# Power.net
KiCad netlist of a schematic drawn in Altium Designer
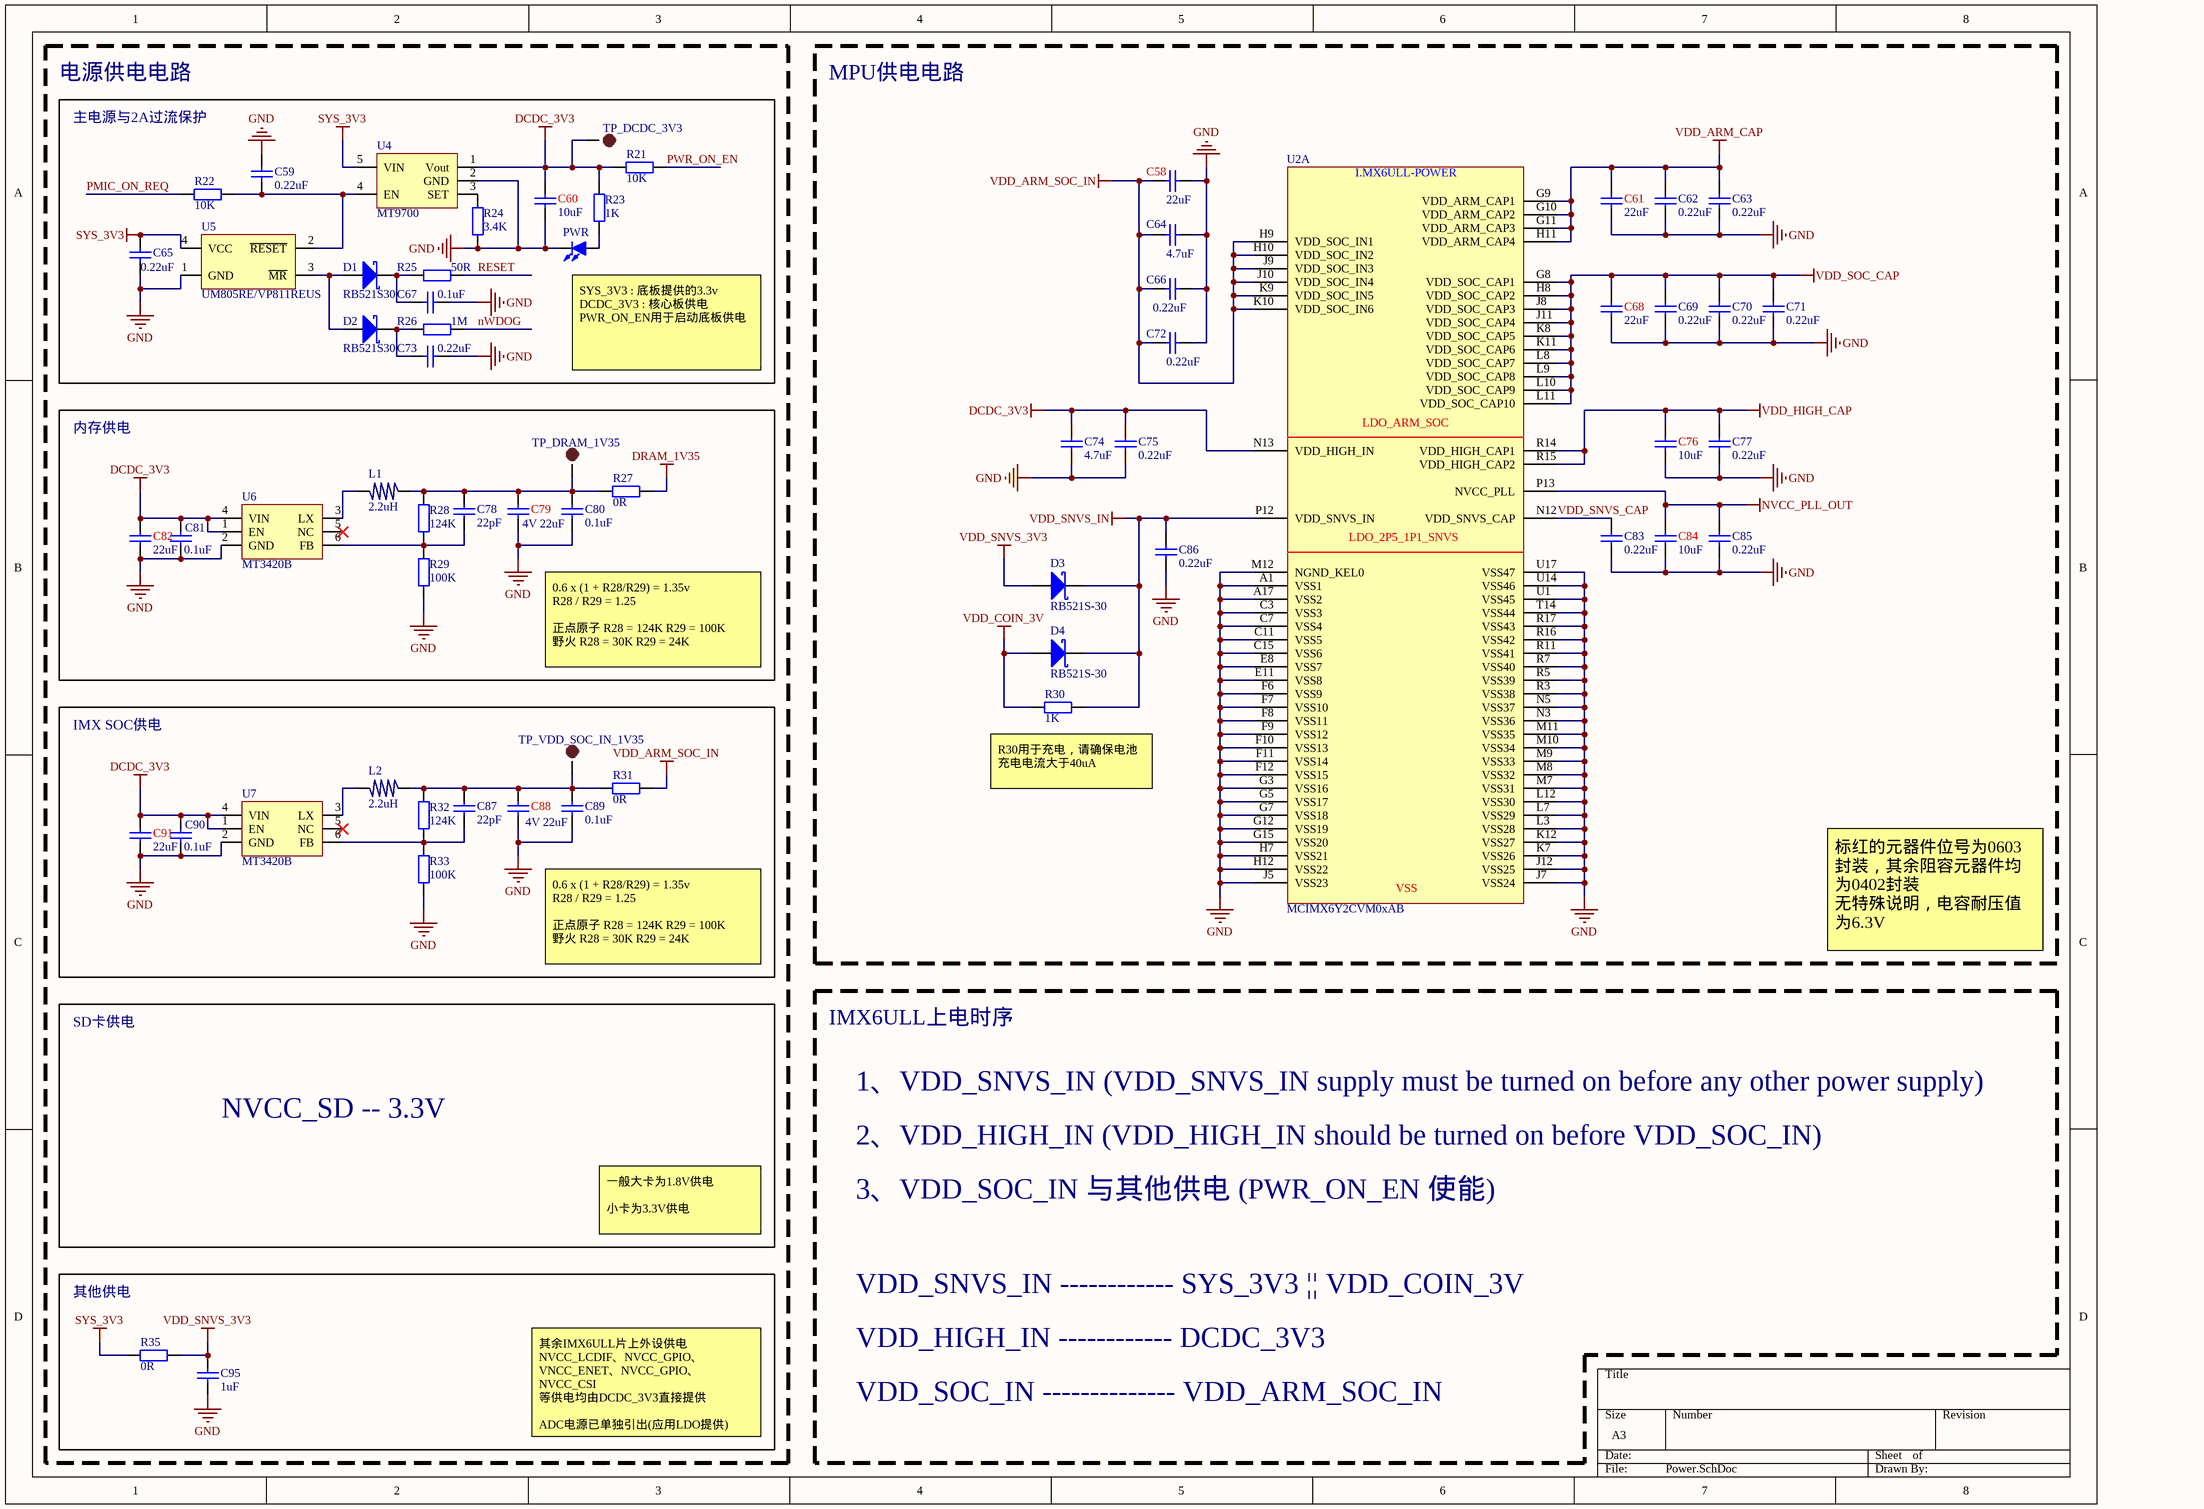
[diagram p0: Power.SchDoc]

(export (version "E")
  (design (tool "Eeschema 10.0.6"))
  (components
    (comp (ref "C58")
      (value "22uF")
      (footprint "0603_C _MINI")
      (description "贴片电容")
      (libsource (lib "My_Devices") (part "0603_C_MINI"))
    )
    (comp (ref "C59")
      (value "0.22uF")
      (footprint "0402_C")
      (description "贴片电容")
      (libsource (lib "My_Devices") (part "0402_C"))
    )
    (comp (ref "C60")
      (value "10uF")
      (footprint "0603_C _MINI")
      (description "贴片电容")
      (libsource (lib "My_Devices") (part "0603_C_MINI"))
    )
    (comp (ref "C61")
      (value "22uF")
      (footprint "0603_C _MINI")
      (description "贴片电容")
      (libsource (lib "My_Devices") (part "0603_C_MINI"))
    )
    (comp (ref "C62")
      (value "0.22uF")
      (footprint "0402_C")
      (description "贴片电容")
      (libsource (lib "My_Devices") (part "0402_C"))
    )
    (comp (ref "C63")
      (value "0.22uF")
      (footprint "0402_C")
      (description "贴片电容")
      (libsource (lib "My_Devices") (part "0402_C"))
    )
    (comp (ref "C64")
      (value "4.7uF")
      (footprint "0402_C")
      (description "贴片电容")
      (libsource (lib "My_Devices") (part "0402_C"))
    )
    (comp (ref "C65")
      (value "0.22uF")
      (footprint "0402_C")
      (description "贴片电容")
      (libsource (lib "My_Devices") (part "0402_C"))
    )
    (comp (ref "C66")
      (value "0.22uF")
      (footprint "0402_C")
      (description "贴片电容")
      (libsource (lib "My_Devices") (part "0402_C"))
    )
    (comp (ref "C67")
      (value "0.1uF")
      (footprint "0402_C")
      (description "贴片电容")
      (libsource (lib "My_Devices") (part "0402_C"))
    )
    (comp (ref "C68")
      (value "22uF")
      (footprint "0603_C _MINI")
      (description "贴片电容")
      (libsource (lib "My_Devices") (part "0603_C_MINI"))
    )
    (comp (ref "C69")
      (value "0.22uF")
      (footprint "0402_C")
      (description "贴片电容")
      (libsource (lib "My_Devices") (part "0402_C"))
    )
    (comp (ref "C70")
      (value "0.22uF")
      (footprint "0402_C")
      (description "贴片电容")
      (libsource (lib "My_Devices") (part "0402_C"))
    )
    (comp (ref "C71")
      (value "0.22uF")
      (footprint "0402_C")
      (description "贴片电容")
      (libsource (lib "My_Devices") (part "0402_C"))
    )
    (comp (ref "C72")
      (value "0.22uF")
      (footprint "0402_C")
      (description "贴片电容")
      (libsource (lib "My_Devices") (part "0402_C"))
    )
    (comp (ref "C73")
      (value "0.22uF")
      (footprint "0402_C")
      (description "贴片电容")
      (libsource (lib "My_Devices") (part "0402_C"))
    )
    (comp (ref "C74")
      (value "4.7uF")
      (footprint "0402_C")
      (description "贴片电容")
      (libsource (lib "My_Devices") (part "0402_C"))
    )
    (comp (ref "C75")
      (value "0.22uF")
      (footprint "0402_C")
      (description "贴片电容")
      (libsource (lib "My_Devices") (part "0402_C"))
    )
    (comp (ref "C76")
      (value "10uF")
      (footprint "0603_C _MINI")
      (description "贴片电容")
      (libsource (lib "My_Devices") (part "0603_C_MINI"))
    )
    (comp (ref "C77")
      (value "0.22uF")
      (footprint "0402_C")
      (description "贴片电容")
      (libsource (lib "My_Devices") (part "0402_C"))
    )
    (comp (ref "C78")
      (value "22pF")
      (footprint "0402_C")
      (description "贴片电容")
      (libsource (lib "My_Devices") (part "0402_C"))
    )
    (comp (ref "C79")
      (value "4V 22uF")
      (footprint "0603_C _MINI")
      (description "贴片电容")
      (libsource (lib "My_Devices") (part "0603_C_MINI"))
    )
    (comp (ref "C80")
      (value "0.1uF")
      (footprint "0402_C")
      (description "贴片电容")
      (libsource (lib "My_Devices") (part "0402_C"))
    )
    (comp (ref "C81")
      (value "0.1uF")
      (footprint "0402_C")
      (description "贴片电容")
      (libsource (lib "My_Devices") (part "0402_C"))
    )
    (comp (ref "C82")
      (value "22uF")
      (footprint "0603_C _MINI")
      (description "贴片电容")
      (libsource (lib "My_Devices") (part "0603_C_MINI"))
    )
    (comp (ref "C83")
      (value "0.22uF")
      (footprint "0402_C")
      (description "贴片电容")
      (libsource (lib "My_Devices") (part "0402_C"))
    )
    (comp (ref "C84")
      (value "10uF")
      (footprint "0603_C _MINI")
      (description "贴片电容")
      (libsource (lib "My_Devices") (part "0603_C_MINI"))
    )
    (comp (ref "C85")
      (value "0.22uF")
      (footprint "0402_C")
      (description "贴片电容")
      (libsource (lib "My_Devices") (part "0402_C"))
    )
    (comp (ref "C86")
      (value "0.22uF")
      (footprint "0402_C")
      (description "贴片电容")
      (libsource (lib "My_Devices") (part "0402_C"))
    )
    (comp (ref "C87")
      (value "22pF")
      (footprint "0402_C")
      (description "贴片电容")
      (libsource (lib "My_Devices") (part "0402_C"))
    )
    (comp (ref "C88")
      (value "4V 22uF")
      (footprint "0603_C _MINI")
      (description "贴片电容")
      (libsource (lib "My_Devices") (part "0603_C_MINI"))
    )
    (comp (ref "C89")
      (value "0.1uF")
      (footprint "0402_C")
      (description "贴片电容")
      (libsource (lib "My_Devices") (part "0402_C"))
    )
    (comp (ref "C90")
      (value "0.1uF")
      (footprint "0402_C")
      (description "贴片电容")
      (libsource (lib "My_Devices") (part "0402_C"))
    )
    (comp (ref "C91")
      (value "22uF")
      (footprint "0603_C _MINI")
      (description "贴片电容")
      (libsource (lib "My_Devices") (part "0603_C_MINI"))
    )
    (comp (ref "C95")
      (value "1uF")
      (footprint "0402_C")
      (description "贴片电容")
      (libsource (lib "My_Devices") (part "0402_C"))
    )
    (comp (ref "D1")
      (value "RB521S30")
      (footprint "SOD-523")
      (libsource (lib "Linux_Base") (part "RB521S30"))
    )
    (comp (ref "D2")
      (value "RB521S30")
      (footprint "SOD-523")
      (libsource (lib "Linux_Base") (part "RB521S30"))
    )
    (comp (ref "D3")
      (value "RB521S-30")
      (footprint "SOD-523")
      (libsource (lib "Linux_Base") (part "RB521S30"))
    )
    (comp (ref "D4")
      (value "RB521S-30")
      (footprint "SOD-523")
      (libsource (lib "Linux_Base") (part "RB521S30"))
    )
    (comp (ref "L1") (value "2.2uH") (footprint "NR3015") (libsource (lib "Linux_Base") (part "L")))
    (comp (ref "L2") (value "2.2uH") (footprint "NR3015") (libsource (lib "Linux_Base") (part "L")))
    (comp (ref "PWR")
      (value "~")
      (footprint "LED 0603B")
      (description "贴片LED")
      (fields (field (name "版权归属") "源创客"))
      (libsource (lib "My_Devices") (part "0603_LED_B"))
    )
    (comp (ref "R21")
      (value "10K")
      (footprint "0402_R")
      (description "贴片电阻")
      (libsource (lib "My_Devices") (part "0402_R"))
    )
    (comp (ref "R22")
      (value "10K")
      (footprint "0402_R")
      (description "贴片电阻")
      (libsource (lib "My_Devices") (part "0402_R"))
    )
    (comp (ref "R23")
      (value "1K")
      (footprint "0402_R")
      (description "贴片电阻")
      (libsource (lib "") (part "0402_R_2"))
    )
    (comp (ref "R24")
      (value "3.4K")
      (footprint "0402_R")
      (description "贴片电阻")
      (libsource (lib "") (part "0402_R_1"))
    )
    (comp (ref "R25")
      (value "50R")
      (footprint "0402_R")
      (description "贴片电阻")
      (libsource (lib "My_Devices") (part "0402_R"))
    )
    (comp (ref "R26")
      (value "1M")
      (footprint "0402_R")
      (description "贴片电阻")
      (libsource (lib "My_Devices") (part "0402_R"))
    )
    (comp (ref "R27")
      (value "0R")
      (footprint "0402_R")
      (description "贴片电阻")
      (libsource (lib "My_Devices") (part "0402_R"))
    )
    (comp (ref "R28")
      (value "124K")
      (footprint "0402_R")
      (description "贴片电阻")
      (libsource (lib "") (part "0402_R_2"))
    )
    (comp (ref "R29")
      (value "100K")
      (footprint "0402_R")
      (description "贴片电阻")
      (libsource (lib "") (part "0402_R_2"))
    )
    (comp (ref "R30")
      (value "1K")
      (footprint "0402_R")
      (description "贴片电阻")
      (libsource (lib "My_Devices") (part "0402_R"))
    )
    (comp (ref "R31")
      (value "0R")
      (footprint "0402_R")
      (description "贴片电阻")
      (libsource (lib "My_Devices") (part "0402_R"))
    )
    (comp (ref "R32")
      (value "124K")
      (footprint "0402_R")
      (description "贴片电阻")
      (libsource (lib "") (part "0402_R_2"))
    )
    (comp (ref "R33")
      (value "100K")
      (footprint "0402_R")
      (description "贴片电阻")
      (libsource (lib "") (part "0402_R_2"))
    )
    (comp (ref "R35")
      (value "0R")
      (footprint "0402_R")
      (description "贴片电阻")
      (libsource (lib "My_Devices") (part "0402_R"))
    )
    (comp (ref "TP_DCDC_3V3")
      (value "SOC_IN")
      (footprint "TP-1.0")
      (description "测试点")
      (libsource (lib "Linux_Base") (part "TEST-POINT"))
    )
    (comp (ref "TP_DRAM_1V35")
      (value "SOC_IN")
      (footprint "TP-1.0")
      (description "测试点")
      (libsource (lib "Linux_Base") (part "TEST-POINT"))
    )
    (comp (ref "TP_VDD_SOC_IN_1V35")
      (value "SOC_IN")
      (footprint "TP-1.0")
      (description "测试点")
      (libsource (lib "Linux_Base") (part "TEST-POINT"))
    )
    (comp (ref "U2")
      (value "MCIMX6Y2CVM0xAB")
      (footprint "BGA289_17x17_0.8Pitch")
      (libsource (lib "Linux_Core") (part "MCIMX6Y2CVM0xAB"))
    )
    (comp (ref "U4")
      (value "MT9700")
      (footprint "SOT23-5L")
      (description "负载开关")
      (libsource (lib "Linux_Base") (part "MT9700"))
    )
    (comp (ref "U5")
      (value "UM805RE/VP811REUS")
      (footprint "SOT143")
      (description "复位芯片")
      (libsource (lib "Linux_Base") (part "UM805RE/VP811REUS"))
    )
    (comp (ref "U6")
      (value "MT3420B")
      (footprint "SOT23-6L")
      (description "DCDC")
      (libsource (lib "Linux_Base") (part "MT3420B"))
    )
    (comp (ref "U7")
      (value "MT3420B")
      (footprint "SOT23-6L")
      (description "DCDC")
      (libsource (lib "Linux_Base") (part "MT3420B"))
    )
  )
  (nets
    (net (code "1") (name "/PMIC_ON_REQ") (class "Default")
      (node (ref "R22") (pin "1") (pinfunction "1_1") (pintype "passive"))
    )
    (net (code "2") (name "/PWR_ON_EN") (class "Default")
      (node (ref "R21") (pin "2") (pinfunction "2_2") (pintype "passive"))
    )
    (net (code "3") (name "/RESET") (class "Default")
      (node (ref "R25") (pin "2") (pinfunction "2_2") (pintype "passive"))
    )
    (net (code "4") (name "/VDD_SNVS_CAP") (class "Default")
      (node (ref "C83") (pin "2") (pinfunction "2_2") (pintype "passive"))
      (node (ref "U2") (pin "N12") (pinfunction "VDD_SNVS_CAP_N12") (pintype "passive"))
    )
    (net (code "5") (name "/nWDOG") (class "Default")
      (node (ref "R26") (pin "2") (pinfunction "2_2") (pintype "passive"))
    )
    (net (code "6") (name "DCDC_3V3") (class "Default")
      (node (ref "C60") (pin "2") (pinfunction "2_2") (pintype "passive"))
      (node (ref "C74") (pin "2") (pinfunction "2_2") (pintype "passive"))
      (node (ref "C75") (pin "2") (pinfunction "2_2") (pintype "passive"))
      (node (ref "C81") (pin "2") (pinfunction "2_2") (pintype "passive"))
      (node (ref "C82") (pin "2") (pinfunction "2_2") (pintype "passive"))
      (node (ref "C90") (pin "2") (pinfunction "2_2") (pintype "passive"))
      (node (ref "C91") (pin "2") (pinfunction "2_2") (pintype "passive"))
      (node (ref "R21") (pin "1") (pinfunction "1_1") (pintype "passive"))
      (node (ref "R23") (pin "2") (pinfunction "2_2") (pintype "passive"))
      (node (ref "TP_DCDC_3V3") (pin "1") (pinfunction "1_1") (pintype "passive"))
      (node (ref "U2") (pin "N13") (pinfunction "VDD_HIGH_IN_N13") (pintype "passive"))
      (node (ref "U4") (pin "1") (pinfunction "Vout_1") (pintype "passive"))
      (node (ref "U6") (pin "1") (pinfunction "EN_1") (pintype "passive"))
      (node (ref "U6") (pin "4") (pinfunction "VIN_4") (pintype "passive"))
      (node (ref "U7") (pin "1") (pinfunction "EN_1") (pintype "passive"))
      (node (ref "U7") (pin "4") (pinfunction "VIN_4") (pintype "passive"))
    )
    (net (code "7") (name "DRAM_1V35") (class "Default")
      (node (ref "R27") (pin "2") (pinfunction "2_2") (pintype "passive"))
    )
    (net (code "8") (name "GND") (class "Default")
      (node (ref "C58") (pin "2") (pinfunction "2_2") (pintype "passive"))
      (node (ref "C59") (pin "2") (pinfunction "2_2") (pintype "passive"))
      (node (ref "C60") (pin "1") (pinfunction "1_1") (pintype "passive"))
      (node (ref "C61") (pin "1") (pinfunction "1_1") (pintype "passive"))
      (node (ref "C62") (pin "1") (pinfunction "1_1") (pintype "passive"))
      (node (ref "C63") (pin "1") (pinfunction "1_1") (pintype "passive"))
      (node (ref "C64") (pin "2") (pinfunction "2_2") (pintype "passive"))
      (node (ref "C65") (pin "1") (pinfunction "1_1") (pintype "passive"))
      (node (ref "C66") (pin "2") (pinfunction "2_2") (pintype "passive"))
      (node (ref "C67") (pin "2") (pinfunction "2_2") (pintype "passive"))
      (node (ref "C68") (pin "1") (pinfunction "1_1") (pintype "passive"))
      (node (ref "C69") (pin "1") (pinfunction "1_1") (pintype "passive"))
      (node (ref "C70") (pin "1") (pinfunction "1_1") (pintype "passive"))
      (node (ref "C71") (pin "1") (pinfunction "1_1") (pintype "passive"))
      (node (ref "C72") (pin "2") (pinfunction "2_2") (pintype "passive"))
      (node (ref "C73") (pin "2") (pinfunction "2_2") (pintype "passive"))
      (node (ref "C74") (pin "1") (pinfunction "1_1") (pintype "passive"))
      (node (ref "C75") (pin "1") (pinfunction "1_1") (pintype "passive"))
      (node (ref "C76") (pin "1") (pinfunction "1_1") (pintype "passive"))
      (node (ref "C77") (pin "1") (pinfunction "1_1") (pintype "passive"))
      (node (ref "C79") (pin "1") (pinfunction "1_1") (pintype "passive"))
      (node (ref "C80") (pin "1") (pinfunction "1_1") (pintype "passive"))
      (node (ref "C81") (pin "1") (pinfunction "1_1") (pintype "passive"))
      (node (ref "C82") (pin "1") (pinfunction "1_1") (pintype "passive"))
      (node (ref "C83") (pin "1") (pinfunction "1_1") (pintype "passive"))
      (node (ref "C84") (pin "1") (pinfunction "1_1") (pintype "passive"))
      (node (ref "C85") (pin "1") (pinfunction "1_1") (pintype "passive"))
      (node (ref "C86") (pin "1") (pinfunction "1_1") (pintype "passive"))
      (node (ref "C88") (pin "1") (pinfunction "1_1") (pintype "passive"))
      (node (ref "C89") (pin "1") (pinfunction "1_1") (pintype "passive"))
      (node (ref "C90") (pin "1") (pinfunction "1_1") (pintype "passive"))
      (node (ref "C91") (pin "1") (pinfunction "1_1") (pintype "passive"))
      (node (ref "C95") (pin "1") (pinfunction "1_1") (pintype "passive"))
      (node (ref "PWR") (pin "2") (pinfunction "K_2") (pintype "passive"))
      (node (ref "R24") (pin "2") (pinfunction "2_2") (pintype "passive"))
      (node (ref "R29") (pin "1") (pinfunction "1_1") (pintype "passive"))
      (node (ref "R33") (pin "1") (pinfunction "1_1") (pintype "passive"))
      (node (ref "U2") (pin "A1") (pinfunction "VSS1_A1") (pintype "passive"))
      (node (ref "U2") (pin "A17") (pinfunction "VSS2_A17") (pintype "passive"))
      (node (ref "U2") (pin "C11") (pinfunction "VSS5_C11") (pintype "passive"))
      (node (ref "U2") (pin "C15") (pinfunction "VSS6_C15") (pintype "passive"))
      (node (ref "U2") (pin "C3") (pinfunction "VSS3_C3") (pintype "passive"))
      (node (ref "U2") (pin "C7") (pinfunction "VSS4_C7") (pintype "passive"))
      (node (ref "U2") (pin "E11") (pinfunction "VSS8_E11") (pintype "passive"))
      (node (ref "U2") (pin "E8") (pinfunction "VSS7_E8") (pintype "passive"))
      (node (ref "U2") (pin "F10") (pinfunction "VSS13_F10") (pintype "passive"))
      (node (ref "U2") (pin "F11") (pinfunction "VSS14_F11") (pintype "passive"))
      (node (ref "U2") (pin "F12") (pinfunction "VSS15_F12") (pintype "passive"))
      (node (ref "U2") (pin "F6") (pinfunction "VSS9_F6") (pintype "passive"))
      (node (ref "U2") (pin "F7") (pinfunction "VSS10_F7") (pintype "passive"))
      (node (ref "U2") (pin "F8") (pinfunction "VSS11_F8") (pintype "passive"))
      (node (ref "U2") (pin "F9") (pinfunction "VSS12_F9") (pintype "passive"))
      (node (ref "U2") (pin "G12") (pinfunction "VSS19_G12") (pintype "passive"))
      (node (ref "U2") (pin "G15") (pinfunction "VSS20_G15") (pintype "passive"))
      (node (ref "U2") (pin "G3") (pinfunction "VSS16_G3") (pintype "passive"))
      (node (ref "U2") (pin "G5") (pinfunction "VSS17_G5") (pintype "passive"))
      (node (ref "U2") (pin "G7") (pinfunction "VSS18_G7") (pintype "passive"))
      (node (ref "U2") (pin "H12") (pinfunction "VSS22_H12") (pintype "passive"))
      (node (ref "U2") (pin "H7") (pinfunction "VSS21_H7") (pintype "passive"))
      (node (ref "U2") (pin "J12") (pinfunction "VSS25_J12") (pintype "passive"))
      (node (ref "U2") (pin "J5") (pinfunction "VSS23_J5") (pintype "passive"))
      (node (ref "U2") (pin "J7") (pinfunction "VSS24_J7") (pintype "passive"))
      (node (ref "U2") (pin "K12") (pinfunction "VSS27_K12") (pintype "passive"))
      (node (ref "U2") (pin "K7") (pinfunction "VSS26_K7") (pintype "passive"))
      (node (ref "U2") (pin "L12") (pinfunction "VSS30_L12") (pintype "passive"))
      (node (ref "U2") (pin "L3") (pinfunction "VSS28_L3") (pintype "passive"))
      (node (ref "U2") (pin "L7") (pinfunction "VSS29_L7") (pintype "passive"))
      (node (ref "U2") (pin "M10") (pinfunction "VSS34_M10") (pintype "passive"))
      (node (ref "U2") (pin "M11") (pinfunction "VSS35_M11") (pintype "passive"))
      (node (ref "U2") (pin "M12") (pinfunction "NGND_KEL0_M12") (pintype "passive"))
      (node (ref "U2") (pin "M7") (pinfunction "VSS31_M7") (pintype "passive"))
      (node (ref "U2") (pin "M8") (pinfunction "VSS32_M8") (pintype "passive"))
      (node (ref "U2") (pin "M9") (pinfunction "VSS33_M9") (pintype "passive"))
      (node (ref "U2") (pin "N3") (pinfunction "VSS36_N3") (pintype "passive"))
      (node (ref "U2") (pin "N5") (pinfunction "VSS37_N5") (pintype "passive"))
      (node (ref "U2") (pin "R11") (pinfunction "VSS41_R11") (pintype "passive"))
      (node (ref "U2") (pin "R16") (pinfunction "VSS42_R16") (pintype "passive"))
      (node (ref "U2") (pin "R17") (pinfunction "VSS43_R17") (pintype "passive"))
      (node (ref "U2") (pin "R3") (pinfunction "VSS38_R3") (pintype "passive"))
      (node (ref "U2") (pin "R5") (pinfunction "VSS39_R5") (pintype "passive"))
      (node (ref "U2") (pin "R7") (pinfunction "VSS40_R7") (pintype "passive"))
      (node (ref "U2") (pin "T14") (pinfunction "VSS44_T14") (pintype "passive"))
      (node (ref "U2") (pin "U1") (pinfunction "VSS45_U1") (pintype "passive"))
      (node (ref "U2") (pin "U14") (pinfunction "VSS46_U14") (pintype "passive"))
      (node (ref "U2") (pin "U17") (pinfunction "VSS47_U17") (pintype "passive"))
      (node (ref "U4") (pin "2") (pinfunction "GND_2") (pintype "passive"))
      (node (ref "U5") (pin "1") (pinfunction "GND_1") (pintype "passive"))
      (node (ref "U6") (pin "2") (pinfunction "GND_2") (pintype "passive"))
      (node (ref "U7") (pin "2") (pinfunction "GND_2") (pintype "passive"))
    )
    (net (code "9") (name "NVCC_PLL_OUT") (class "Default")
      (node (ref "C84") (pin "2") (pinfunction "2_2") (pintype "passive"))
      (node (ref "C85") (pin "2") (pinfunction "2_2") (pintype "passive"))
      (node (ref "U2") (pin "P13") (pinfunction "NVCC_PLL_P13") (pintype "passive"))
    )
    (net (code "10") (name "Net-(C78-Pad2)") (class "Default")
      (node (ref "C78") (pin "2") (pinfunction "2_2") (pintype "passive"))
      (node (ref "C79") (pin "2") (pinfunction "2_2") (pintype "passive"))
      (node (ref "C80") (pin "2") (pinfunction "2_2") (pintype "passive"))
      (node (ref "L1") (pin "1") (pintype "passive"))
      (node (ref "R27") (pin "1") (pinfunction "1_1") (pintype "passive"))
      (node (ref "R28") (pin "2") (pinfunction "2_2") (pintype "passive"))
      (node (ref "TP_DRAM_1V35") (pin "1") (pinfunction "1_1") (pintype "passive"))
    )
    (net (code "11") (name "Net-(C87-Pad2)") (class "Default")
      (node (ref "C87") (pin "2") (pinfunction "2_2") (pintype "passive"))
      (node (ref "C88") (pin "2") (pinfunction "2_2") (pintype "passive"))
      (node (ref "C89") (pin "2") (pinfunction "2_2") (pintype "passive"))
      (node (ref "L2") (pin "1") (pintype "passive"))
      (node (ref "R31") (pin "1") (pinfunction "1_1") (pintype "passive"))
      (node (ref "R32") (pin "2") (pinfunction "2_2") (pintype "passive"))
      (node (ref "TP_VDD_SOC_IN_1V35") (pin "1") (pinfunction "1_1") (pintype "passive"))
    )
    (net (code "12") (name "Net-(D1-A)") (class "Default")
      (node (ref "D1") (pin "1") (pinfunction "A_1") (pintype "passive"))
      (node (ref "D2") (pin "1") (pinfunction "A_1") (pintype "passive"))
      (node (ref "U5") (pin "3") (pinfunction "~{MR}_3") (pintype "passive"))
    )
    (net (code "13") (name "Net-(D1-C)") (class "Default")
      (node (ref "C67") (pin "1") (pinfunction "1_1") (pintype "passive"))
      (node (ref "D1") (pin "2") (pinfunction "C_2") (pintype "passive"))
      (node (ref "R25") (pin "1") (pinfunction "1_1") (pintype "passive"))
    )
    (net (code "14") (name "Net-(D2-C)") (class "Default")
      (node (ref "C73") (pin "1") (pinfunction "1_1") (pintype "passive"))
      (node (ref "D2") (pin "2") (pinfunction "C_2") (pintype "passive"))
      (node (ref "R26") (pin "1") (pinfunction "1_1") (pintype "passive"))
    )
    (net (code "15") (name "Net-(PWR-A)") (class "Default")
      (node (ref "PWR") (pin "1") (pinfunction "A_1") (pintype "passive"))
      (node (ref "R23") (pin "1") (pinfunction "1_1") (pintype "passive"))
    )
    (net (code "16") (name "Net-(U4-EN)") (class "Default")
      (node (ref "C59") (pin "1") (pinfunction "1_1") (pintype "passive"))
      (node (ref "R22") (pin "2") (pinfunction "2_2") (pintype "passive"))
      (node (ref "U4") (pin "4") (pinfunction "EN_4") (pintype "passive"))
      (node (ref "U5") (pin "2") (pinfunction "~{RESET}_2") (pintype "passive"))
    )
    (net (code "17") (name "Net-(U4-SET)") (class "Default")
      (node (ref "R24") (pin "1") (pinfunction "1_1") (pintype "passive"))
      (node (ref "U4") (pin "3") (pinfunction "SET_3") (pintype "passive"))
    )
    (net (code "18") (name "Net-(U6-FB)") (class "Default")
      (node (ref "C78") (pin "1") (pinfunction "1_1") (pintype "passive"))
      (node (ref "R28") (pin "1") (pinfunction "1_1") (pintype "passive"))
      (node (ref "R29") (pin "2") (pinfunction "2_2") (pintype "passive"))
      (node (ref "U6") (pin "6") (pinfunction "FB_6") (pintype "passive"))
    )
    (net (code "19") (name "Net-(U6-LX)") (class "Default")
      (node (ref "L1") (pin "2") (pintype "passive"))
      (node (ref "U6") (pin "3") (pinfunction "LX_3") (pintype "passive"))
    )
    (net (code "20") (name "Net-(U7-FB)") (class "Default")
      (node (ref "C87") (pin "1") (pinfunction "1_1") (pintype "passive"))
      (node (ref "R32") (pin "1") (pinfunction "1_1") (pintype "passive"))
      (node (ref "R33") (pin "2") (pinfunction "2_2") (pintype "passive"))
      (node (ref "U7") (pin "6") (pinfunction "FB_6") (pintype "passive"))
    )
    (net (code "21") (name "Net-(U7-LX)") (class "Default")
      (node (ref "L2") (pin "2") (pintype "passive"))
      (node (ref "U7") (pin "3") (pinfunction "LX_3") (pintype "passive"))
    )
    (net (code "22") (name "SYS_3V3") (class "Default")
      (node (ref "C65") (pin "2") (pinfunction "2_2") (pintype "passive"))
      (node (ref "R35") (pin "1") (pinfunction "1_1") (pintype "passive"))
      (node (ref "U4") (pin "5") (pinfunction "VIN_5") (pintype "passive"))
      (node (ref "U5") (pin "4") (pinfunction "VCC_4") (pintype "passive"))
    )
    (net (code "23") (name "VDD_ARM_CAP") (class "Default")
      (node (ref "C61") (pin "2") (pinfunction "2_2") (pintype "passive"))
      (node (ref "C62") (pin "2") (pinfunction "2_2") (pintype "passive"))
      (node (ref "C63") (pin "2") (pinfunction "2_2") (pintype "passive"))
      (node (ref "U2") (pin "G10") (pinfunction "VDD_ARM_CAP2_G10") (pintype "passive"))
      (node (ref "U2") (pin "G11") (pinfunction "VDD_ARM_CAP3_G11") (pintype "passive"))
      (node (ref "U2") (pin "G9") (pinfunction "VDD_ARM_CAP1_G9") (pintype "passive"))
      (node (ref "U2") (pin "H11") (pinfunction "VDD_ARM_CAP4_H11") (pintype "passive"))
    )
    (net (code "24") (name "VDD_ARM_SOC_IN") (class "Default")
      (node (ref "C58") (pin "1") (pinfunction "1_1") (pintype "passive"))
      (node (ref "C64") (pin "1") (pinfunction "1_1") (pintype "passive"))
      (node (ref "C66") (pin "1") (pinfunction "1_1") (pintype "passive"))
      (node (ref "C72") (pin "1") (pinfunction "1_1") (pintype "passive"))
      (node (ref "R31") (pin "2") (pinfunction "2_2") (pintype "passive"))
      (node (ref "U2") (pin "H10") (pinfunction "VDD_SOC_IN2_H10") (pintype "passive"))
      (node (ref "U2") (pin "H9") (pinfunction "VDD_SOC_IN1_H9") (pintype "passive"))
      (node (ref "U2") (pin "J10") (pinfunction "VDD_SOC_IN4_J10") (pintype "passive"))
      (node (ref "U2") (pin "J9") (pinfunction "VDD_SOC_IN3_J9") (pintype "passive"))
      (node (ref "U2") (pin "K10") (pinfunction "VDD_SOC_IN6_K10") (pintype "passive"))
      (node (ref "U2") (pin "K9") (pinfunction "VDD_SOC_IN5_K9") (pintype "passive"))
    )
    (net (code "25") (name "VDD_COIN_3V") (class "Default")
      (node (ref "D4") (pin "1") (pinfunction "A_1") (pintype "passive"))
      (node (ref "R30") (pin "1") (pinfunction "1_1") (pintype "passive"))
    )
    (net (code "26") (name "VDD_HIGH_CAP") (class "Default")
      (node (ref "C76") (pin "2") (pinfunction "2_2") (pintype "passive"))
      (node (ref "C77") (pin "2") (pinfunction "2_2") (pintype "passive"))
      (node (ref "U2") (pin "R14") (pinfunction "VDD_HIGH_CAP1_R14") (pintype "passive"))
      (node (ref "U2") (pin "R15") (pinfunction "VDD_HIGH_CAP2_R15") (pintype "passive"))
    )
    (net (code "27") (name "VDD_SNVS_3V3") (class "Default")
      (node (ref "C95") (pin "2") (pinfunction "2_2") (pintype "passive"))
      (node (ref "D3") (pin "1") (pinfunction "A_1") (pintype "passive"))
      (node (ref "R35") (pin "2") (pinfunction "2_2") (pintype "passive"))
    )
    (net (code "28") (name "VDD_SNVS_IN") (class "Default")
      (node (ref "C86") (pin "2") (pinfunction "2_2") (pintype "passive"))
      (node (ref "D3") (pin "2") (pinfunction "C_2") (pintype "passive"))
      (node (ref "D4") (pin "2") (pinfunction "C_2") (pintype "passive"))
      (node (ref "R30") (pin "2") (pinfunction "2_2") (pintype "passive"))
      (node (ref "U2") (pin "P12") (pinfunction "VDD_SNVS_IN_P12") (pintype "passive"))
    )
    (net (code "29") (name "VDD_SOC_CAP") (class "Default")
      (node (ref "C68") (pin "2") (pinfunction "2_2") (pintype "passive"))
      (node (ref "C69") (pin "2") (pinfunction "2_2") (pintype "passive"))
      (node (ref "C70") (pin "2") (pinfunction "2_2") (pintype "passive"))
      (node (ref "C71") (pin "2") (pinfunction "2_2") (pintype "passive"))
      (node (ref "U2") (pin "G8") (pinfunction "VDD_SOC_CAP1_G8") (pintype "passive"))
      (node (ref "U2") (pin "H8") (pinfunction "VDD_SOC_CAP2_H8") (pintype "passive"))
      (node (ref "U2") (pin "J11") (pinfunction "VDD_SOC_CAP4_J11") (pintype "passive"))
      (node (ref "U2") (pin "J8") (pinfunction "VDD_SOC_CAP3_J8") (pintype "passive"))
      (node (ref "U2") (pin "K11") (pinfunction "VDD_SOC_CAP6_K11") (pintype "passive"))
      (node (ref "U2") (pin "K8") (pinfunction "VDD_SOC_CAP5_K8") (pintype "passive"))
      (node (ref "U2") (pin "L10") (pinfunction "VDD_SOC_CAP9_L10") (pintype "passive"))
      (node (ref "U2") (pin "L11") (pinfunction "VDD_SOC_CAP10_L11") (pintype "passive"))
      (node (ref "U2") (pin "L8") (pinfunction "VDD_SOC_CAP7_L8") (pintype "passive"))
      (node (ref "U2") (pin "L9") (pinfunction "VDD_SOC_CAP8_L9") (pintype "passive"))
    )
    (net (code "30") (name "unconnected-(U6-NC-Pad5)") (class "Default")
      (node (ref "U6") (pin "5") (pinfunction "NC_5") (pintype "passive+no_connect"))
    )
    (net (code "31") (name "unconnected-(U7-NC-Pad5)") (class "Default")
      (node (ref "U7") (pin "5") (pinfunction "NC_5") (pintype "passive+no_connect"))
    )
  )
)
